# 60W_FM_PA.net
KiCad netlist of a schematic drawn in EAGLE
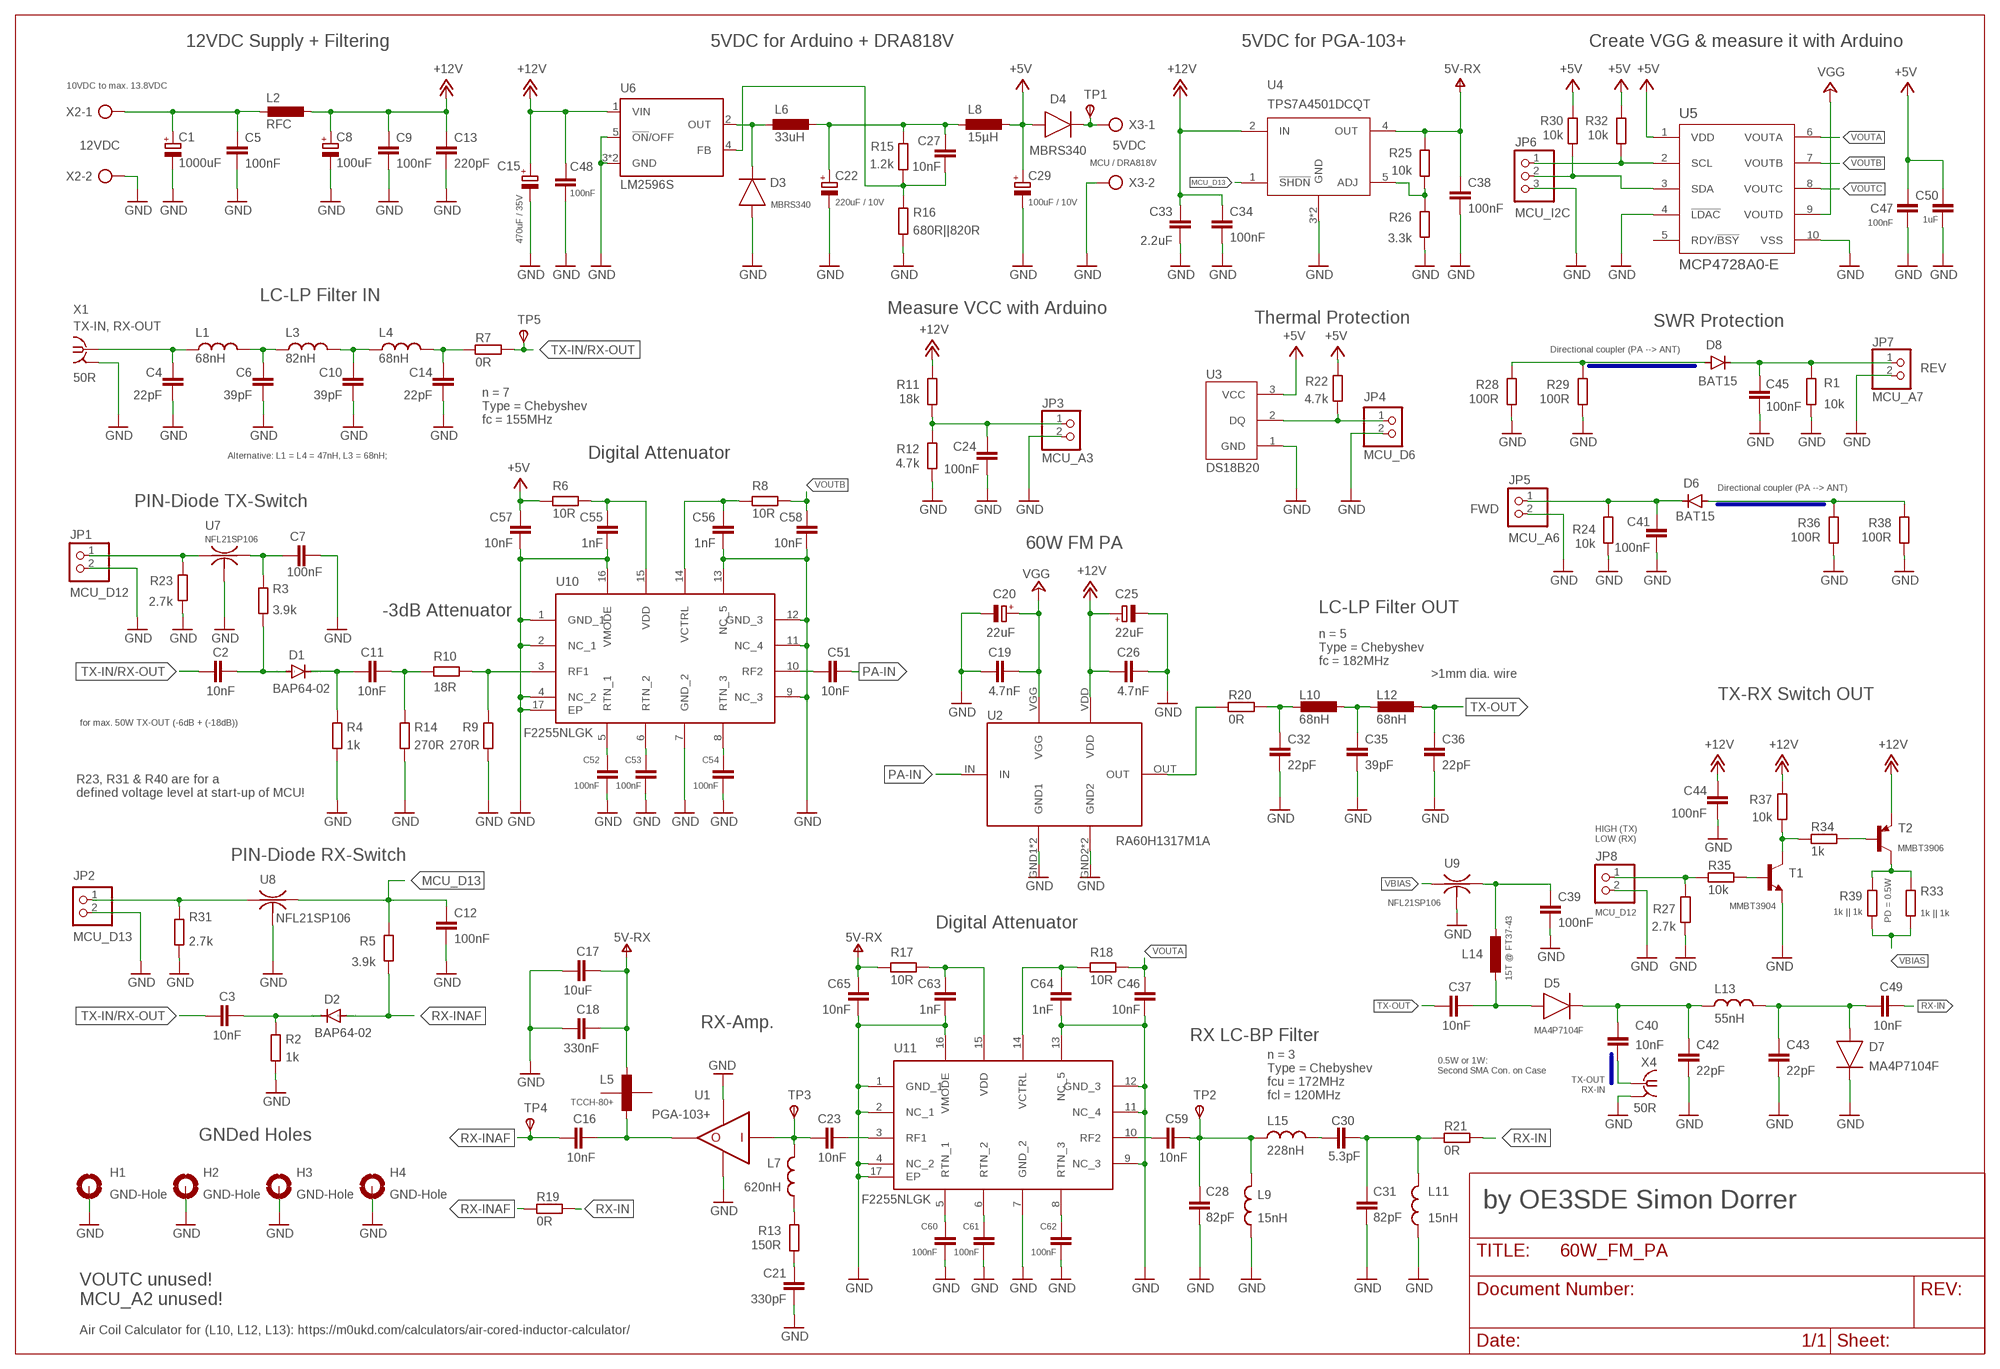
[diagram p0: schematic, sheet 1]

(export (version "E")
  (design (tool "Eeschema 10.0.6"))
  (components
    (comp (ref "C1")
      (value "1000uF")
      (footprint "eagle-import:CAPAE1030X1050N")
      (libsource (lib "eagle-import") (part "C-POLECAP-10.5MM_"))
    )
    (comp (ref "C2")
      (value "10nF")
      (footprint "eagle-import:CAPC2012X110")
      (libsource (lib "eagle-import") (part "CCHIP-0805(2012-METRIC)_"))
    )
    (comp (ref "C3")
      (value "10nF")
      (footprint "eagle-import:CAPC2012X110")
      (libsource (lib "eagle-import") (part "CCHIP-0805(2012-METRIC)_"))
    )
    (comp (ref "C4")
      (value "22pF")
      (footprint "eagle-import:CAPC2012X110")
      (libsource (lib "eagle-import") (part "CCHIP-0805(2012-METRIC)_"))
    )
    (comp (ref "C5")
      (value "100nF")
      (footprint "eagle-import:CAPC2012X110")
      (libsource (lib "eagle-import") (part "CCHIP-0805(2012-METRIC)_"))
    )
    (comp (ref "C6")
      (value "39pF")
      (footprint "eagle-import:CAPC2012X110")
      (libsource (lib "eagle-import") (part "CCHIP-0805(2012-METRIC)_"))
    )
    (comp (ref "C7")
      (value "100nF")
      (footprint "eagle-import:CAPC2012X110")
      (libsource (lib "eagle-import") (part "CCHIP-0805(2012-METRIC)_"))
    )
    (comp (ref "C8")
      (value "100uF")
      (footprint "eagle-import:CAPAE1030X1050N")
      (libsource (lib "eagle-import") (part "C-POLECAP-10.5MM_"))
    )
    (comp (ref "C9")
      (value "100nF")
      (footprint "eagle-import:CAPC2012X110")
      (libsource (lib "eagle-import") (part "CCHIP-0805(2012-METRIC)_"))
    )
    (comp (ref "C10")
      (value "39pF")
      (footprint "eagle-import:CAPC2012X110")
      (libsource (lib "eagle-import") (part "CCHIP-0805(2012-METRIC)_"))
    )
    (comp (ref "C11")
      (value "10nF")
      (footprint "eagle-import:CAPC2012X110")
      (libsource (lib "eagle-import") (part "CCHIP-0805(2012-METRIC)_"))
    )
    (comp (ref "C12")
      (value "100nF")
      (footprint "eagle-import:CAPC2012X110")
      (libsource (lib "eagle-import") (part "CCHIP-0805(2012-METRIC)_"))
    )
    (comp (ref "C13")
      (value "220pF")
      (footprint "eagle-import:CAPC2012X110")
      (libsource (lib "eagle-import") (part "CCHIP-0805(2012-METRIC)_"))
    )
    (comp (ref "C14")
      (value "22pF")
      (footprint "eagle-import:CAPC2012X110")
      (libsource (lib "eagle-import") (part "CCHIP-0805(2012-METRIC)_"))
    )
    (comp (ref "C15")
      (value "470uF / 35V")
      (footprint "eagle-import:CAPAE1030X1050N")
      (libsource (lib "eagle-import") (part "C-POLECAP-10.5MM_"))
    )
    (comp (ref "C16")
      (value "10nF")
      (footprint "eagle-import:CAPC2012X110")
      (libsource (lib "eagle-import") (part "CCHIP-0805(2012-METRIC)_"))
    )
    (comp (ref "C17")
      (value "10uF")
      (footprint "eagle-import:CAPC2012X110")
      (libsource (lib "eagle-import") (part "CCHIP-0805(2012-METRIC)_"))
    )
    (comp (ref "C18")
      (value "330nF")
      (footprint "eagle-import:CAPC2012X110")
      (libsource (lib "eagle-import") (part "CCHIP-0805(2012-METRIC)_"))
    )
    (comp (ref "C19")
      (value "4.7nF")
      (footprint "eagle-import:CAPC2012X110")
      (libsource (lib "eagle-import") (part "CCHIP-0805(2012-METRIC)_"))
    )
    (comp (ref "C20")
      (value "22uF")
      (footprint "eagle-import:SMC_D")
      (libsource (lib "eagle-import") (part "CPOL-EUSMCD"))
    )
    (comp (ref "C21")
      (value "330pF")
      (footprint "eagle-import:CAPC2012X110")
      (libsource (lib "eagle-import") (part "CCHIP-0805(2012-METRIC)_"))
    )
    (comp (ref "C22")
      (value "220uF / 10V")
      (footprint "eagle-import:CAPMP7343X310N")
      (libsource (lib "eagle-import") (part "C-POLTANTALUM-2917(7343-METRIC)_"))
    )
    (comp (ref "C23")
      (value "10nF")
      (footprint "eagle-import:CAPC2012X110")
      (libsource (lib "eagle-import") (part "CCHIP-0805(2012-METRIC)_"))
    )
    (comp (ref "C24")
      (value "100nF")
      (footprint "eagle-import:CAPC2012X110")
      (libsource (lib "eagle-import") (part "CCHIP-0805(2012-METRIC)_"))
    )
    (comp (ref "C25")
      (value "22uF")
      (footprint "eagle-import:SMC_D")
      (libsource (lib "eagle-import") (part "CPOL-EUSMCD"))
    )
    (comp (ref "C26")
      (value "4.7nF")
      (footprint "eagle-import:CAPC2012X110")
      (libsource (lib "eagle-import") (part "CCHIP-0805(2012-METRIC)_"))
    )
    (comp (ref "C27")
      (value "10nF")
      (footprint "eagle-import:CAPC2012X110")
      (libsource (lib "eagle-import") (part "CCHIP-0805(2012-METRIC)_"))
    )
    (comp (ref "C28")
      (value "82pF")
      (footprint "eagle-import:CAPC2012X110")
      (libsource (lib "eagle-import") (part "CCHIP-0805(2012-METRIC)_"))
    )
    (comp (ref "C29")
      (value "100uF / 10V")
      (footprint "eagle-import:CAPMP7343X310N")
      (libsource (lib "eagle-import") (part "C-POLTANTALUM-2917(7343-METRIC)_"))
    )
    (comp (ref "C30")
      (value "5.3pF")
      (footprint "eagle-import:CAPC2012X110")
      (libsource (lib "eagle-import") (part "CCHIP-0805(2012-METRIC)_"))
    )
    (comp (ref "C31")
      (value "82pF")
      (footprint "eagle-import:CAPC2012X110")
      (libsource (lib "eagle-import") (part "CCHIP-0805(2012-METRIC)_"))
    )
    (comp (ref "C32")
      (value "22pF")
      (footprint "eagle-import:CAPC3216X135")
      (libsource (lib "eagle-import") (part "CCHIP-1206(3216-METRIC)_"))
    )
    (comp (ref "C33")
      (value "2.2uF")
      (footprint "eagle-import:CAPC2012X110")
      (libsource (lib "eagle-import") (part "CCHIP-0805(2012-METRIC)_"))
    )
    (comp (ref "C34")
      (value "100nF")
      (footprint "eagle-import:CAPC2012X110")
      (libsource (lib "eagle-import") (part "CCHIP-0805(2012-METRIC)_"))
    )
    (comp (ref "C35")
      (value "39pF")
      (footprint "eagle-import:CAPC3216X135")
      (libsource (lib "eagle-import") (part "CCHIP-1206(3216-METRIC)_"))
    )
    (comp (ref "C36")
      (value "22pF")
      (footprint "eagle-import:CAPC3216X135")
      (libsource (lib "eagle-import") (part "CCHIP-1206(3216-METRIC)_"))
    )
    (comp (ref "C37")
      (value "10nF")
      (footprint "eagle-import:CAPC3216X135")
      (libsource (lib "eagle-import") (part "CCHIP-1206(3216-METRIC)_"))
    )
    (comp (ref "C38")
      (value "100nF")
      (footprint "eagle-import:CAPC2012X110")
      (libsource (lib "eagle-import") (part "CCHIP-0805(2012-METRIC)_"))
    )
    (comp (ref "C39")
      (value "100nF")
      (footprint "eagle-import:CAPC2012X110")
      (libsource (lib "eagle-import") (part "CCHIP-0805(2012-METRIC)_"))
    )
    (comp (ref "C40")
      (value "10nF")
      (footprint "eagle-import:CAPC3216X135")
      (libsource (lib "eagle-import") (part "CCHIP-1206(3216-METRIC)_"))
    )
    (comp (ref "C41")
      (value "100nF")
      (footprint "eagle-import:CAPC2012X110")
      (libsource (lib "eagle-import") (part "CCHIP-0805(2012-METRIC)_"))
    )
    (comp (ref "C42")
      (value "22pF")
      (footprint "eagle-import:CAPC3216X135")
      (libsource (lib "eagle-import") (part "CCHIP-1206(3216-METRIC)_"))
    )
    (comp (ref "C43")
      (value "22pF")
      (footprint "eagle-import:CAPC3216X135")
      (libsource (lib "eagle-import") (part "CCHIP-1206(3216-METRIC)_"))
    )
    (comp (ref "C44")
      (value "100nF")
      (footprint "eagle-import:CAPC2012X110")
      (libsource (lib "eagle-import") (part "CCHIP-0805(2012-METRIC)_"))
    )
    (comp (ref "C45")
      (value "100nF")
      (footprint "eagle-import:CAPC2012X110")
      (libsource (lib "eagle-import") (part "CCHIP-0805(2012-METRIC)_"))
    )
    (comp (ref "C46")
      (value "10nF")
      (footprint "eagle-import:CAPC2012X110")
      (libsource (lib "eagle-import") (part "CCHIP-0805(2012-METRIC)_"))
    )
    (comp (ref "C47")
      (value "100nF")
      (footprint "eagle-import:CAPC2012X110")
      (libsource (lib "eagle-import") (part "CCHIP-0805(2012-METRIC)_"))
    )
    (comp (ref "C48")
      (value "100nF")
      (footprint "eagle-import:CAPC2012X110")
      (libsource (lib "eagle-import") (part "CCHIP-0805(2012-METRIC)_"))
    )
    (comp (ref "C49")
      (value "10nF")
      (footprint "eagle-import:CAPC3216X135")
      (libsource (lib "eagle-import") (part "CCHIP-1206(3216-METRIC)_"))
    )
    (comp (ref "C50")
      (value "1uF")
      (footprint "eagle-import:CAPC2012X110")
      (libsource (lib "eagle-import") (part "CCHIP-0805(2012-METRIC)_"))
    )
    (comp (ref "C51")
      (value "10nF")
      (footprint "eagle-import:CAPC2012X110")
      (libsource (lib "eagle-import") (part "CCHIP-0805(2012-METRIC)_"))
    )
    (comp (ref "C52")
      (value "100nF")
      (footprint "eagle-import:CAPC1608X85")
      (libsource (lib "eagle-import") (part "CCHIP-0603(1608-METRIC)_"))
    )
    (comp (ref "C53")
      (value "100nF")
      (footprint "eagle-import:CAPC1608X85")
      (libsource (lib "eagle-import") (part "CCHIP-0603(1608-METRIC)_"))
    )
    (comp (ref "C54")
      (value "100nF")
      (footprint "eagle-import:CAPC1608X85")
      (libsource (lib "eagle-import") (part "CCHIP-0603(1608-METRIC)_"))
    )
    (comp (ref "C55")
      (value "1nF")
      (footprint "eagle-import:CAPC2012X110")
      (libsource (lib "eagle-import") (part "CCHIP-0805(2012-METRIC)_"))
    )
    (comp (ref "C56")
      (value "1nF")
      (footprint "eagle-import:CAPC2012X110")
      (libsource (lib "eagle-import") (part "CCHIP-0805(2012-METRIC)_"))
    )
    (comp (ref "C57")
      (value "10nF")
      (footprint "eagle-import:CAPC2012X110")
      (libsource (lib "eagle-import") (part "CCHIP-0805(2012-METRIC)_"))
    )
    (comp (ref "C58")
      (value "10nF")
      (footprint "eagle-import:CAPC2012X110")
      (libsource (lib "eagle-import") (part "CCHIP-0805(2012-METRIC)_"))
    )
    (comp (ref "C59")
      (value "10nF")
      (footprint "eagle-import:CAPC2012X110")
      (libsource (lib "eagle-import") (part "CCHIP-0805(2012-METRIC)_"))
    )
    (comp (ref "C60")
      (value "100nF")
      (footprint "eagle-import:CAPC1608X85")
      (libsource (lib "eagle-import") (part "CCHIP-0603(1608-METRIC)_"))
    )
    (comp (ref "C61")
      (value "100nF")
      (footprint "eagle-import:CAPC1608X85")
      (libsource (lib "eagle-import") (part "CCHIP-0603(1608-METRIC)_"))
    )
    (comp (ref "C62")
      (value "100nF")
      (footprint "eagle-import:CAPC1608X85")
      (libsource (lib "eagle-import") (part "CCHIP-0603(1608-METRIC)_"))
    )
    (comp (ref "C63")
      (value "1nF")
      (footprint "eagle-import:CAPC2012X110")
      (libsource (lib "eagle-import") (part "CCHIP-0805(2012-METRIC)_"))
    )
    (comp (ref "C64")
      (value "1nF")
      (footprint "eagle-import:CAPC2012X110")
      (libsource (lib "eagle-import") (part "CCHIP-0805(2012-METRIC)_"))
    )
    (comp (ref "C65")
      (value "10nF")
      (footprint "eagle-import:CAPC2012X110")
      (libsource (lib "eagle-import") (part "CCHIP-0805(2012-METRIC)_"))
    )
    (comp (ref "D1")
      (value "BAP64-02")
      (footprint "eagle-import:SOD523")
      (libsource (lib "eagle-import") (part "DIODE-SOD523"))
    )
    (comp (ref "D2")
      (value "BAP64-02")
      (footprint "eagle-import:SOD523")
      (libsource (lib "eagle-import") (part "DIODE-SOD523"))
    )
    (comp (ref "D3")
      (value "MBRS340")
      (footprint "eagle-import:DIOM7959X625N")
      (libsource (lib "eagle-import") (part "DIODEDO-214AB(SMC)"))
    )
    (comp (ref "D4")
      (value "MBRS340")
      (footprint "eagle-import:DIOM7959X625N")
      (libsource (lib "eagle-import") (part "DIODEDO-214AB(SMC)"))
    )
    (comp (ref "D5")
      (value "MA4P7104F")
      (footprint "eagle-import:SODFL5336X110")
      (libsource (lib "eagle-import") (part "DIODEDO-221-AA_"))
    )
    (comp (ref "D6")
      (value "BAT15")
      (footprint "eagle-import:SOD-323")
      (fields
        (field (name "DIGIKEY_PART_NUMBER") "1N4148WSFSTR-ND")
        (field (name "MANUFACTURER") "Diodes Incorporated")
        (field (name "MPN") "1N4148WS")
        (field (name "CREATED_BY") "PCBLayout.com")
      )
      (libsource (lib "eagle-import") (part "1N4148WS"))
    )
    (comp (ref "D7")
      (value "MA4P7104F")
      (footprint "eagle-import:SODFL5336X110")
      (libsource (lib "eagle-import") (part "DIODEDO-221-AA_"))
    )
    (comp (ref "D8")
      (value "BAT15")
      (footprint "eagle-import:SOD-323")
      (fields
        (field (name "DIGIKEY_PART_NUMBER") "1N4148WSFSTR-ND")
        (field (name "MANUFACTURER") "Diodes Incorporated")
        (field (name "MPN") "1N4148WS")
        (field (name "CREATED_BY") "PCBLayout.com")
      )
      (libsource (lib "eagle-import") (part "1N4148WS"))
    )
    (comp (ref "H1")
      (value "GND-Hole")
      (footprint "eagle-import:3,0-PAD")
      (libsource (lib "eagle-import") (part "MOUNT-PAD-ROUND3.0"))
    )
    (comp (ref "H2")
      (value "GND-Hole")
      (footprint "eagle-import:3,0-PAD")
      (libsource (lib "eagle-import") (part "MOUNT-PAD-ROUND3.0"))
    )
    (comp (ref "H3")
      (value "GND-Hole")
      (footprint "eagle-import:3,0-PAD")
      (libsource (lib "eagle-import") (part "MOUNT-PAD-ROUND3.0"))
    )
    (comp (ref "H4")
      (value "GND-Hole")
      (footprint "eagle-import:3,0-PAD")
      (libsource (lib "eagle-import") (part "MOUNT-PAD-ROUND3.0"))
    )
    (comp (ref "JP1")
      (value "MCU_D12")
      (footprint "eagle-import:1X02")
      (libsource (lib "eagle-import") (part "PINHD-1X2"))
    )
    (comp (ref "JP2")
      (value "MCU_D13")
      (footprint "eagle-import:1X02")
      (libsource (lib "eagle-import") (part "PINHD-1X2"))
    )
    (comp (ref "JP3")
      (value "MCU_A3")
      (footprint "eagle-import:1X02")
      (libsource (lib "eagle-import") (part "PINHD-1X2"))
    )
    (comp (ref "JP4")
      (value "MCU_D6")
      (footprint "eagle-import:1X02")
      (libsource (lib "eagle-import") (part "PINHD-1X2"))
    )
    (comp (ref "JP5")
      (value "MCU_A6")
      (footprint "eagle-import:1X02")
      (libsource (lib "eagle-import") (part "PINHD-1X2"))
    )
    (comp (ref "JP6")
      (value "MCU_I2C")
      (footprint "eagle-import:1X03")
      (libsource (lib "eagle-import") (part "PINHD-1X3"))
    )
    (comp (ref "JP7")
      (value "MCU_A7")
      (footprint "eagle-import:1X02")
      (libsource (lib "eagle-import") (part "PINHD-1X2"))
    )
    (comp (ref "JP8")
      (value "MCU_D12")
      (footprint "eagle-import:1X02")
      (libsource (lib "eagle-import") (part "PINHD-1X2"))
    )
    (comp (ref "L1")
      (value "68nH")
      (footprint "eagle-import:INDC2009X120")
      (libsource (lib "eagle-import") (part "LCHIP-0805(2012-METRIC)_"))
    )
    (comp (ref "L2")
      (value "RFC")
      (footprint "eagle-import:T50-6SMD")
      (libsource (lib "eagle-import") (part "T50-6"))
    )
    (comp (ref "L3")
      (value "82nH")
      (footprint "eagle-import:INDC2009X120")
      (libsource (lib "eagle-import") (part "LCHIP-0805(2012-METRIC)_"))
    )
    (comp (ref "L4")
      (value "68nH")
      (footprint "eagle-import:INDC2009X120")
      (libsource (lib "eagle-import") (part "LCHIP-0805(2012-METRIC)_"))
    )
    (comp (ref "L5")
      (value "TCCH-80+")
      (footprint "eagle-import:TCCH-80")
      (libsource (lib "eagle-import") (part "TCCH-80+"))
    )
    (comp (ref "L6")
      (value "33uH")
      (footprint "eagle-import:1260")
      (libsource (lib "eagle-import") (part "L-EU"))
    )
    (comp (ref "L7")
      (value "620nH")
      (footprint "eagle-import:INDC2009X120")
      (libsource (lib "eagle-import") (part "LCHIP-0805(2012-METRIC)_"))
    )
    (comp (ref "L8")
      (value "15µH")
      (footprint "eagle-import:1260")
      (libsource (lib "eagle-import") (part "L-EU"))
    )
    (comp (ref "L9")
      (value "15nH")
      (footprint "eagle-import:INDC3216X190")
      (libsource (lib "eagle-import") (part "LCHIP-1206(3216-METRIC)_"))
    )
    (comp (ref "L10")
      (value "68nH")
      (footprint "eagle-import:AIR-COIL-SMD")
      (libsource (lib "eagle-import") (part "AIR-COIL"))
    )
    (comp (ref "L11")
      (value "15nH")
      (footprint "eagle-import:INDC3216X190")
      (libsource (lib "eagle-import") (part "LCHIP-1206(3216-METRIC)_"))
    )
    (comp (ref "L12")
      (value "68nH")
      (footprint "eagle-import:AIR-COIL-SMD")
      (libsource (lib "eagle-import") (part "AIR-COIL"))
    )
    (comp (ref "L13")
      (value "55nH")
      (footprint "eagle-import:INDC3216X190")
      (libsource (lib "eagle-import") (part "LCHIP-1206(3216-METRIC)_"))
    )
    (comp (ref "L14")
      (value "15T @ FT37-43")
      (footprint "eagle-import:AIR-COIL-SMD")
      (libsource (lib "eagle-import") (part "AIR-COIL"))
    )
    (comp (ref "L15")
      (value "228nH")
      (footprint "eagle-import:INDC3216X190")
      (libsource (lib "eagle-import") (part "LCHIP-1206(3216-METRIC)_"))
    )
    (comp (ref "R1")
      (value "10k")
      (footprint "eagle-import:RESC2012X65")
      (libsource (lib "eagle-import") (part "RCHIP-0805(2012-METRIC)_"))
    )
    (comp (ref "R2")
      (value "1k")
      (footprint "eagle-import:RESC2012X65")
      (libsource (lib "eagle-import") (part "RCHIP-0805(2012-METRIC)_"))
    )
    (comp (ref "R3")
      (value "3.9k")
      (footprint "eagle-import:RESC2012X65")
      (libsource (lib "eagle-import") (part "RCHIP-0805(2012-METRIC)_"))
    )
    (comp (ref "R4")
      (value "1k")
      (footprint "eagle-import:RESC2012X65")
      (libsource (lib "eagle-import") (part "RCHIP-0805(2012-METRIC)_"))
    )
    (comp (ref "R5")
      (value "3.9k")
      (footprint "eagle-import:RESC2012X65")
      (libsource (lib "eagle-import") (part "RCHIP-0805(2012-METRIC)_"))
    )
    (comp (ref "R6")
      (value "10R")
      (footprint "eagle-import:RESC2012X65")
      (libsource (lib "eagle-import") (part "RCHIP-0805(2012-METRIC)_"))
    )
    (comp (ref "R7")
      (value "0R")
      (footprint "eagle-import:RESC2012X65")
      (libsource (lib "eagle-import") (part "RCHIP-0805(2012-METRIC)_"))
    )
    (comp (ref "R8")
      (value "10R")
      (footprint "eagle-import:RESC2012X65")
      (libsource (lib "eagle-import") (part "RCHIP-0805(2012-METRIC)_"))
    )
    (comp (ref "R9")
      (value "270R")
      (footprint "eagle-import:RESC2012X65")
      (libsource (lib "eagle-import") (part "RCHIP-0805(2012-METRIC)_"))
    )
    (comp (ref "R10")
      (value "18R")
      (footprint "eagle-import:RESC2012X65")
      (libsource (lib "eagle-import") (part "RCHIP-0805(2012-METRIC)_"))
    )
    (comp (ref "R11")
      (value "18k")
      (footprint "eagle-import:RESC2012X65")
      (libsource (lib "eagle-import") (part "RCHIP-0805(2012-METRIC)_"))
    )
    (comp (ref "R12")
      (value "4.7k")
      (footprint "eagle-import:RESC2012X65")
      (libsource (lib "eagle-import") (part "RCHIP-0805(2012-METRIC)_"))
    )
    (comp (ref "R13")
      (value "150R")
      (footprint "eagle-import:RESC2012X65")
      (libsource (lib "eagle-import") (part "RCHIP-0805(2012-METRIC)_"))
    )
    (comp (ref "R14")
      (value "270R")
      (footprint "eagle-import:RESC2012X65")
      (libsource (lib "eagle-import") (part "RCHIP-0805(2012-METRIC)_"))
    )
    (comp (ref "R15")
      (value "1.2k")
      (footprint "eagle-import:RESC2012X65")
      (libsource (lib "eagle-import") (part "RCHIP-0805(2012-METRIC)_"))
    )
    (comp (ref "R16")
      (value "680R||820R")
      (footprint "eagle-import:RESC2012X65")
      (libsource (lib "eagle-import") (part "RCHIP-0805(2012-METRIC)_"))
    )
    (comp (ref "R17")
      (value "10R")
      (footprint "eagle-import:RESC2012X65")
      (libsource (lib "eagle-import") (part "RCHIP-0805(2012-METRIC)_"))
    )
    (comp (ref "R18")
      (value "10R")
      (footprint "eagle-import:RESC2012X65")
      (libsource (lib "eagle-import") (part "RCHIP-0805(2012-METRIC)_"))
    )
    (comp (ref "R19")
      (value "0R")
      (footprint "eagle-import:RESC2012X65")
      (libsource (lib "eagle-import") (part "RCHIP-0805(2012-METRIC)_"))
    )
    (comp (ref "R20")
      (value "0R")
      (footprint "eagle-import:RESC3216X70")
      (libsource (lib "eagle-import") (part "RCHIP-1206(3216-METRIC)_"))
    )
    (comp (ref "R21")
      (value "0R")
      (footprint "eagle-import:RESC2012X65")
      (libsource (lib "eagle-import") (part "RCHIP-0805(2012-METRIC)_"))
    )
    (comp (ref "R22")
      (value "4.7k")
      (footprint "eagle-import:RESC2012X65")
      (libsource (lib "eagle-import") (part "RCHIP-0805(2012-METRIC)_"))
    )
    (comp (ref "R23")
      (value "2.7k")
      (footprint "eagle-import:RESC2012X65")
      (libsource (lib "eagle-import") (part "RCHIP-0805(2012-METRIC)_"))
    )
    (comp (ref "R24")
      (value "10k")
      (footprint "eagle-import:RESC2012X65")
      (libsource (lib "eagle-import") (part "RCHIP-0805(2012-METRIC)_"))
    )
    (comp (ref "R25")
      (value "10k")
      (footprint "eagle-import:RESC2012X65")
      (libsource (lib "eagle-import") (part "RCHIP-0805(2012-METRIC)_"))
    )
    (comp (ref "R26")
      (value "3.3k")
      (footprint "eagle-import:RESC2012X65")
      (libsource (lib "eagle-import") (part "RCHIP-0805(2012-METRIC)_"))
    )
    (comp (ref "R27")
      (value "2.7k")
      (footprint "eagle-import:RESC2012X65")
      (libsource (lib "eagle-import") (part "RCHIP-0805(2012-METRIC)_"))
    )
    (comp (ref "R28")
      (value "100R")
      (footprint "eagle-import:RESC2012X65")
      (libsource (lib "eagle-import") (part "RCHIP-0805(2012-METRIC)_"))
    )
    (comp (ref "R29")
      (value "100R")
      (footprint "eagle-import:RESC2012X65")
      (libsource (lib "eagle-import") (part "RCHIP-0805(2012-METRIC)_"))
    )
    (comp (ref "R30")
      (value "10k")
      (footprint "eagle-import:RESC2012X65")
      (libsource (lib "eagle-import") (part "RCHIP-0805(2012-METRIC)_"))
    )
    (comp (ref "R31")
      (value "2.7k")
      (footprint "eagle-import:RESC2012X65")
      (libsource (lib "eagle-import") (part "RCHIP-0805(2012-METRIC)_"))
    )
    (comp (ref "R32")
      (value "10k")
      (footprint "eagle-import:RESC2012X65")
      (libsource (lib "eagle-import") (part "RCHIP-0805(2012-METRIC)_"))
    )
    (comp (ref "R33")
      (value "1k || 1k")
      (footprint "eagle-import:RESC2012X65")
      (libsource (lib "eagle-import") (part "RCHIP-0805(2012-METRIC)_"))
    )
    (comp (ref "R34")
      (value "1k")
      (footprint "eagle-import:RESC2012X65")
      (libsource (lib "eagle-import") (part "RCHIP-0805(2012-METRIC)_"))
    )
    (comp (ref "R35")
      (value "10k")
      (footprint "eagle-import:RESC2012X65")
      (libsource (lib "eagle-import") (part "RCHIP-0805(2012-METRIC)_"))
    )
    (comp (ref "R36")
      (value "100R")
      (footprint "eagle-import:RESC2012X65")
      (libsource (lib "eagle-import") (part "RCHIP-0805(2012-METRIC)_"))
    )
    (comp (ref "R37")
      (value "10k")
      (footprint "eagle-import:RESC2012X65")
      (libsource (lib "eagle-import") (part "RCHIP-0805(2012-METRIC)_"))
    )
    (comp (ref "R38")
      (value "100R")
      (footprint "eagle-import:RESC2012X65")
      (libsource (lib "eagle-import") (part "RCHIP-0805(2012-METRIC)_"))
    )
    (comp (ref "R39")
      (value "1k || 1k")
      (footprint "eagle-import:RESC2012X65")
      (libsource (lib "eagle-import") (part "RCHIP-0805(2012-METRIC)_"))
    )
    (comp (ref "T1")
      (value "MMBT3904")
      (footprint "eagle-import:SOT23-BEC")
      (libsource (lib "eagle-import") (part "-NPN-SOT23-BECMMBT3904LT1"))
    )
    (comp (ref "T2")
      (value "MMBT3906")
      (footprint "eagle-import:SOT23-BEC")
      (libsource (lib "eagle-import") (part "MMBT3906SMDLT1"))
    )
    (comp (ref "TP1")
      (value "TPSTP10SQ")
      (footprint "eagle-import:TP10SQ")
      (libsource (lib "eagle-import") (part "TPSTP10SQ"))
    )
    (comp (ref "TP2")
      (value "TPSTP10SQ")
      (footprint "eagle-import:TP10SQ")
      (libsource (lib "eagle-import") (part "TPSTP10SQ"))
    )
    (comp (ref "TP3")
      (value "TPSTP10SQ")
      (footprint "eagle-import:TP10SQ")
      (libsource (lib "eagle-import") (part "TPSTP10SQ"))
    )
    (comp (ref "TP4")
      (value "TPSTP10SQ")
      (footprint "eagle-import:TP10SQ")
      (libsource (lib "eagle-import") (part "TPSTP10SQ"))
    )
    (comp (ref "TP5")
      (value "TPSTP10SQ")
      (footprint "eagle-import:TP10SQ")
      (libsource (lib "eagle-import") (part "TPSTP10SQ"))
    )
    (comp (ref "U1")
      (value "PGA-103+")
      (footprint "eagle-import:SOT89")
      (libsource (lib "eagle-import") (part "PGA-103+"))
    )
    (comp (ref "U2")
      (value "RA60H1317M1A")
      (footprint "eagle-import:RA60H1317M1A")
      (libsource (lib "eagle-import") (part "RA60H1317M1A"))
    )
    (comp (ref "U3")
      (value "DS18B20")
      (footprint "eagle-import:21-0248A_MXM")
      (fields (field (name "MANUFACTURER_PART_NUMBER") "DS1810-10"))
      (libsource (lib "eagle-import") (part "DS1810-10"))
    )
    (comp (ref "U4")
      (value "TPS7A4501DCQT")
      (footprint "eagle-import:DCQ6")
      (fields
        (field (name "GENERIC_PART_NUMBER") "TPS7A4533")
        (field (name "MANUFACTURER") "Texas Instruments")
      )
      (libsource (lib "eagle-import") (part "TPS7A4501DCQT"))
    )
    (comp (ref "U5")
      (value "MCP4728A0-E")
      (footprint "eagle-import:MSOP10_MC_MCH-M")
      (fields
        (field (name "MANUFACTURER_PART_NUMBER") "MCP4728A0-E/UN")
        (field (name "COPYRIGHT") "Copyright (C) 2018 Accelerated Designs. All rights reserved")
      )
      (libsource (lib "eagle-import") (part "MCP4728A0-E/UNMSOP10_MC_MCH-M"))
    )
    (comp (ref "U6")
      (value "LM2596S")
      (footprint "eagle-import:TO263-5")
      (fields (field (name "MF") "NATIONAL SEMICONDUCTOR") (field (name "MPN") "LM2596S-ADJ/NOPB"))
      (libsource (lib "eagle-import") (part "LM2596S"))
    )
    (comp (ref "U7")
      (value "NFL21SP106")
      (footprint "eagle-import:NFM21C")
      (libsource (lib "eagle-import") (part "NFL21SP106"))
    )
    (comp (ref "U8")
      (value "NFL21SP106")
      (footprint "eagle-import:NFM21C")
      (libsource (lib "eagle-import") (part "NFL21SP106"))
    )
    (comp (ref "U9")
      (value "NFL21SP106")
      (footprint "eagle-import:NFM21C")
      (libsource (lib "eagle-import") (part "NFL21SP106"))
    )
    (comp (ref "U10")
      (value "F2255NLGK")
      (footprint "eagle-import:QFN50P300X300X100-17N")
      (fields (field (name "MOUSER_PART_NUMBER") "972-F2255NLGK"))
      (libsource (lib "eagle-import") (part "F2255NLGK"))
    )
    (comp (ref "U11")
      (value "F2255NLGK")
      (footprint "eagle-import:QFN50P300X300X100-17N")
      (fields (field (name "MOUSER_PART_NUMBER") "972-F2255NLGK"))
      (libsource (lib "eagle-import") (part "F2255NLGK"))
    )
    (comp (ref "X1")
      (value "TX-IN, RX-OUT")
      (footprint "eagle-import:J502-ND-142-0711-821_826")
      (fields (field (name "MF") "JOHNSON COMPONENTS") (field (name "MPN") "142-0711-821"))
      (libsource (lib "eagle-import") (part "SMA-142-0711-821/826"))
    )
    (comp (ref "X2")
      (value "12VDC")
      (footprint "eagle-import:AK300_2")
      (libsource (lib "eagle-import") (part "AK300/2"))
    )
    (comp (ref "X3")
      (value "5VDC")
      (footprint "eagle-import:AK300_2")
      (libsource (lib "eagle-import") (part "AK300/2"))
    )
    (comp (ref "X4")
      (value "50R")
      (footprint "eagle-import:J502-ND-142-0711-821_826")
      (fields (field (name "MF") "JOHNSON COMPONENTS") (field (name "MPN") "142-0711-821"))
      (libsource (lib "eagle-import") (part "SMA-142-0711-821/826"))
    )
  )
  (nets
    (net (code "4") (name "+5V") (class "Default")
      (node (ref "C29") (pin "1") (pinfunction "+_1") (pintype "passive"))
      (node (ref "C47") (pin "2") (pinfunction "2_2") (pintype "passive"))
      (node (ref "C50") (pin "2") (pinfunction "2_2") (pintype "passive"))
      (node (ref "C57") (pin "1") (pinfunction "1_1") (pintype "passive"))
      (node (ref "D4") (pin "2") (pinfunction "A_2") (pintype "passive"))
      (node (ref "L8") (pin "-") (pinfunction "2_-") (pintype "passive"))
      (node (ref "R22") (pin "2") (pinfunction "2_2") (pintype "passive"))
      (node (ref "R30") (pin "1") (pinfunction "1_1") (pintype "passive"))
      (node (ref "R32") (pin "1") (pinfunction "1_1") (pintype "passive"))
      (node (ref "R6") (pin "1") (pinfunction "1_1") (pintype "passive"))
      (node (ref "U3") (pin "3") (pinfunction "VCC_3") (pintype "power_in"))
      (node (ref "U5") (pin "1") (pinfunction "VDD_1") (pintype "power_in"))
    )
    (net (code "5") (name "+12V") (class "Default")
      (node (ref "C13") (pin "2") (pinfunction "2_2") (pintype "passive"))
      (node (ref "C15") (pin "1") (pinfunction "+_1") (pintype "passive"))
      (node (ref "C25") (pin "+") (pinfunction "+_+") (pintype "passive"))
      (node (ref "C26") (pin "1") (pinfunction "1_1") (pintype "passive"))
      (node (ref "C33") (pin "2") (pinfunction "2_2") (pintype "passive"))
      (node (ref "C34") (pin "2") (pinfunction "2_2") (pintype "passive"))
      (node (ref "C44") (pin "2") (pinfunction "2_2") (pintype "passive"))
      (node (ref "C48") (pin "2") (pinfunction "2_2") (pintype "passive"))
      (node (ref "C8") (pin "1") (pinfunction "+_1") (pintype "passive"))
      (node (ref "C9") (pin "2") (pinfunction "2_2") (pintype "passive"))
      (node (ref "L2") (pin "P$2") (pinfunction "2_P$2") (pintype "passive"))
      (node (ref "R11") (pin "2") (pinfunction "2_2") (pintype "passive"))
      (node (ref "R37") (pin "1") (pinfunction "1_1") (pintype "passive"))
      (node (ref "T2") (pin "E") (pinfunction "E_E") (pintype "passive"))
      (node (ref "U2") (pin "VDD") (pinfunction "VDD_VDD") (pintype "power_in"))
      (node (ref "U4") (pin "2") (pinfunction "IN_2") (pintype "input"))
      (node (ref "U6") (pin "1") (pinfunction "VIN_1") (pintype "input"))
    )
    (net (code "7") (name "5V-RX") (class "Default")
      (node (ref "C17") (pin "1") (pinfunction "1_1") (pintype "passive"))
      (node (ref "C18") (pin "1") (pinfunction "1_1") (pintype "passive"))
      (node (ref "C38") (pin "2") (pinfunction "2_2") (pintype "passive"))
      (node (ref "C65") (pin "1") (pinfunction "1_1") (pintype "passive"))
      (node (ref "L5") (pin "DC") (pinfunction "DC_DC") (pintype "passive"))
      (node (ref "R17") (pin "1") (pinfunction "1_1") (pintype "passive"))
      (node (ref "R25") (pin "1") (pinfunction "1_1") (pintype "passive"))
      (node (ref "U4") (pin "4") (pinfunction "OUT_4") (pintype "output"))
    )
    (net (code "8") (name "GND") (class "Default")
      (node (ref "C1") (pin "2") (pinfunction "-_2") (pintype "passive"))
      (node (ref "C10") (pin "2") (pinfunction "2_2") (pintype "passive"))
      (node (ref "C12") (pin "1") (pinfunction "1_1") (pintype "passive"))
      (node (ref "C13") (pin "1") (pinfunction "1_1") (pintype "passive"))
      (node (ref "C14") (pin "2") (pinfunction "2_2") (pintype "passive"))
      (node (ref "C15") (pin "2") (pinfunction "-_2") (pintype "passive"))
      (node (ref "C17") (pin "2") (pinfunction "2_2") (pintype "passive"))
      (node (ref "C18") (pin "2") (pinfunction "2_2") (pintype "passive"))
      (node (ref "C19") (pin "1") (pinfunction "1_1") (pintype "passive"))
      (node (ref "C20") (pin "-") (pinfunction "-_-") (pintype "passive"))
      (node (ref "C21") (pin "1") (pinfunction "1_1") (pintype "passive"))
      (node (ref "C22") (pin "2") (pinfunction "-_2") (pintype "passive"))
      (node (ref "C24") (pin "1") (pinfunction "1_1") (pintype "passive"))
      (node (ref "C25") (pin "-") (pinfunction "-_-") (pintype "passive"))
      (node (ref "C26") (pin "2") (pinfunction "2_2") (pintype "passive"))
      (node (ref "C28") (pin "2") (pinfunction "2_2") (pintype "passive"))
      (node (ref "C29") (pin "2") (pinfunction "-_2") (pintype "passive"))
      (node (ref "C31") (pin "2") (pinfunction "2_2") (pintype "passive"))
      (node (ref "C32") (pin "2") (pinfunction "2_2") (pintype "passive"))
      (node (ref "C33") (pin "1") (pinfunction "1_1") (pintype "passive"))
      (node (ref "C34") (pin "1") (pinfunction "1_1") (pintype "passive"))
      (node (ref "C35") (pin "2") (pinfunction "2_2") (pintype "passive"))
      (node (ref "C36") (pin "2") (pinfunction "2_2") (pintype "passive"))
      (node (ref "C38") (pin "1") (pinfunction "1_1") (pintype "passive"))
      (node (ref "C39") (pin "1") (pinfunction "1_1") (pintype "passive"))
      (node (ref "C4") (pin "2") (pinfunction "2_2") (pintype "passive"))
      (node (ref "C41") (pin "2") (pinfunction "2_2") (pintype "passive"))
      (node (ref "C42") (pin "2") (pinfunction "2_2") (pintype "passive"))
      (node (ref "C43") (pin "2") (pinfunction "2_2") (pintype "passive"))
      (node (ref "C44") (pin "1") (pinfunction "1_1") (pintype "passive"))
      (node (ref "C45") (pin "2") (pinfunction "2_2") (pintype "passive"))
      (node (ref "C46") (pin "2") (pinfunction "2_2") (pintype "passive"))
      (node (ref "C47") (pin "1") (pinfunction "1_1") (pintype "passive"))
      (node (ref "C48") (pin "1") (pinfunction "1_1") (pintype "passive"))
      (node (ref "C5") (pin "1") (pinfunction "1_1") (pintype "passive"))
      (node (ref "C50") (pin "1") (pinfunction "1_1") (pintype "passive"))
      (node (ref "C52") (pin "2") (pinfunction "2_2") (pintype "passive"))
      (node (ref "C53") (pin "2") (pinfunction "2_2") (pintype "passive"))
      (node (ref "C54") (pin "2") (pinfunction "2_2") (pintype "passive"))
      (node (ref "C55") (pin "2") (pinfunction "2_2") (pintype "passive"))
      (node (ref "C56") (pin "2") (pinfunction "2_2") (pintype "passive"))
      (node (ref "C57") (pin "2") (pinfunction "2_2") (pintype "passive"))
      (node (ref "C58") (pin "2") (pinfunction "2_2") (pintype "passive"))
      (node (ref "C6") (pin "2") (pinfunction "2_2") (pintype "passive"))
      (node (ref "C60") (pin "2") (pinfunction "2_2") (pintype "passive"))
      (node (ref "C61") (pin "2") (pinfunction "2_2") (pintype "passive"))
      (node (ref "C62") (pin "2") (pinfunction "2_2") (pintype "passive"))
      (node (ref "C63") (pin "2") (pinfunction "2_2") (pintype "passive"))
      (node (ref "C64") (pin "2") (pinfunction "2_2") (pintype "passive"))
      (node (ref "C65") (pin "2") (pinfunction "2_2") (pintype "passive"))
      (node (ref "C7") (pin "1") (pinfunction "1_1") (pintype "passive"))
      (node (ref "C8") (pin "2") (pinfunction "-_2") (pintype "passive"))
      (node (ref "C9") (pin "1") (pinfunction "1_1") (pintype "passive"))
      (node (ref "D3") (pin "2") (pinfunction "A_2") (pintype "passive"))
      (node (ref "D7") (pin "1") (pinfunction "C_1") (pintype "passive"))
      (node (ref "H1") (pin "B3,0") (pinfunction "MOUNT_B3,0") (pintype "passive"))
      (node (ref "H2") (pin "B3,0") (pinfunction "MOUNT_B3,0") (pintype "passive"))
      (node (ref "H3") (pin "B3,0") (pinfunction "MOUNT_B3,0") (pintype "passive"))
      (node (ref "H4") (pin "B3,0") (pinfunction "MOUNT_B3,0") (pintype "passive"))
      (node (ref "JP1") (pin "2") (pinfunction "2_2") (pintype "passive"))
      (node (ref "JP2") (pin "2") (pinfunction "2_2") (pintype "passive"))
      (node (ref "JP3") (pin "2") (pinfunction "2_2") (pintype "passive"))
      (node (ref "JP4") (pin "2") (pinfunction "2_2") (pintype "passive"))
      (node (ref "JP5") (pin "2") (pinfunction "2_2") (pintype "passive"))
      (node (ref "JP6") (pin "3") (pinfunction "3_3") (pintype "passive"))
      (node (ref "JP7") (pin "2") (pinfunction "2_2") (pintype "passive"))
      (node (ref "JP8") (pin "2") (pinfunction "2_2") (pintype "passive"))
      (node (ref "L11") (pin "1") (pinfunction "1_1") (pintype "passive"))
      (node (ref "L9") (pin "1") (pinfunction "1_1") (pintype "passive"))
      (node (ref "R1") (pin "2") (pinfunction "2_2") (pintype "passive"))
      (node (ref "R12") (pin "1") (pinfunction "1_1") (pintype "passive"))
      (node (ref "R14") (pin "2") (pinfunction "2_2") (pintype "passive"))
      (node (ref "R16") (pin "1") (pinfunction "1_1") (pintype "passive"))
      (node (ref "R2") (pin "2") (pinfunction "2_2") (pintype "passive"))
      (node (ref "R23") (pin "2") (pinfunction "2_2") (pintype "passive"))
      (node (ref "R24") (pin "1") (pinfunction "1_1") (pintype "passive"))
      (node (ref "R26") (pin "2") (pinfunction "2_2") (pintype "passive"))
      (node (ref "R27") (pin "2") (pinfunction "2_2") (pintype "passive"))
      (node (ref "R28") (pin "1") (pinfunction "1_1") (pintype "passive"))
      (node (ref "R29") (pin "1") (pinfunction "1_1") (pintype "passive"))
      (node (ref "R31") (pin "2") (pinfunction "2_2") (pintype "passive"))
      (node (ref "R36") (pin "1") (pinfunction "1_1") (pintype "passive"))
      (node (ref "R38") (pin "1") (pinfunction "1_1") (pintype "passive"))
      (node (ref "R4") (pin "2") (pinfunction "2_2") (pintype "passive"))
      (node (ref "R9") (pin "2") (pinfunction "2_2") (pintype "passive"))
      (node (ref "T1") (pin "E") (pinfunction "E_E") (pintype "passive"))
      (node (ref "U1") (pin "2") (pinfunction "GND1_2") (pintype "power_in"))
      (node (ref "U1") (pin "2@1") (pinfunction "GND2_2@1") (pintype "power_in"))
      (node (ref "U10") (pin "1") (pinfunction "GND_1_1") (pintype "bidirectional"))
      (node (ref "U10") (pin "11") (pinfunction "NC_4_11") (pintype "bidirectional"))
      (node (ref "U10") (pin "12") (pinfunction "GND_3_12") (pintype "bidirectional"))
      (node (ref "U10") (pin "13") (pinfunction "NC_5_13") (pintype "bidirectional"))
      (node (ref "U10") (pin "16") (pinfunction "VMODE_16") (pintype "bidirectional"))
      (node (ref "U10") (pin "17") (pinfunction "EP_17") (pintype "bidirectional"))
      (node (ref "U10") (pin "2") (pinfunction "NC_1_2") (pintype "bidirectional"))
      (node (ref "U10") (pin "4") (pinfunction "NC_2_4") (pintype "bidirectional"))
      (node (ref "U10") (pin "7") (pinfunction "GND_2_7") (pintype "bidirectional"))
      (node (ref "U10") (pin "9") (pinfunction "NC_3_9") (pintype "bidirectional"))
      (node (ref "U11") (pin "1") (pinfunction "GND_1_1") (pintype "bidirectional"))
      (node (ref "U11") (pin "11") (pinfunction "NC_4_11") (pintype "bidirectional"))
      (node (ref "U11") (pin "12") (pinfunction "GND_3_12") (pintype "bidirectional"))
      (node (ref "U11") (pin "13") (pinfunction "NC_5_13") (pintype "bidirectional"))
      (node (ref "U11") (pin "16") (pinfunction "VMODE_16") (pintype "bidirectional"))
      (node (ref "U11") (pin "17") (pinfunction "EP_17") (pintype "bidirectional"))
      (node (ref "U11") (pin "2") (pinfunction "NC_1_2") (pintype "bidirectional"))
      (node (ref "U11") (pin "4") (pinfunction "NC_2_4") (pintype "bidirectional"))
      (node (ref "U11") (pin "7") (pinfunction "GND_2_7") (pintype "bidirectional"))
      (node (ref "U11") (pin "9") (pinfunction "NC_3_9") (pintype "bidirectional"))
      (node (ref "U2") (pin "GND1") (pinfunction "GND1_GND1") (pintype "power_in"))
      (node (ref "U2") (pin "GND2") (pinfunction "GND2_GND2") (pintype "power_in"))
      (node (ref "U2") (pin "GND3") (pinfunction "GND1_GND3") (pintype "power_in"))
      (node (ref "U2") (pin "GND4") (pinfunction "GND2_GND4") (pintype "power_in"))
      (node (ref "U3") (pin "1") (pinfunction "GND_1") (pintype "power_in"))
      (node (ref "U4") (pin "3") (pinfunction "GND_3") (pintype "power_in"))
      (node (ref "U4") (pin "6") (pinfunction "GND_6") (pintype "power_in"))
      (node (ref "U5") (pin "10") (pinfunction "VSS_10") (pintype "power_in"))
      (node (ref "U5") (pin "4") (pinfunction "~{LDAC}_4") (pintype "input"))
      (node (ref "U6") (pin "3") (pinfunction "GND_3") (pintype "power_in"))
      (node (ref "U6") (pin "5") (pinfunction "~{ON}/OFF_5") (pintype "input"))
      (node (ref "U6") (pin "6") (pinfunction "GND_6") (pintype "power_in"))
      (node (ref "U7") (pin "2@1") (pinfunction "2_2@1") (pintype "passive"))
      (node (ref "U7") (pin "2@2") (pinfunction "2_2@2") (pintype "passive"))
      (node (ref "U8") (pin "2@1") (pinfunction "2_2@1") (pintype "passive"))
      (node (ref "U8") (pin "2@2") (pinfunction "2_2@2") (pintype "passive"))
      (node (ref "U9") (pin "2@1") (pinfunction "2_2@1") (pintype "passive"))
      (node (ref "U9") (pin "2@2") (pinfunction "2_2@2") (pintype "passive"))
      (node (ref "X1") (pin "G@1") (pinfunction "2_G@1") (pintype "passive"))
      (node (ref "X1") (pin "G@2") (pinfunction "2_G@2") (pintype "passive"))
      (node (ref "X1") (pin "G@3") (pinfunction "2_G@3") (pintype "passive"))
      (node (ref "X1") (pin "G@4") (pinfunction "2_G@4") (pintype "passive"))
      (node (ref "X2") (pin "2") (pinfunction "KL_2") (pintype "passive"))
      (node (ref "X3") (pin "2") (pinfunction "KL_2") (pintype "passive"))
      (node (ref "X4") (pin "G@1") (pinfunction "2_G@1") (pintype "passive"))
      (node (ref "X4") (pin "G@2") (pinfunction "2_G@2") (pintype "passive"))
      (node (ref "X4") (pin "G@3") (pinfunction "2_G@3") (pintype "passive"))
      (node (ref "X4") (pin "G@4") (pinfunction "2_G@4") (pintype "passive"))
    )
    (net (code "9") (name "MCU_D13") (class "Default")
      (node (ref "C12") (pin "2") (pinfunction "2_2") (pintype "passive"))
      (node (ref "R5") (pin "1") (pinfunction "1_1") (pintype "passive"))
      (node (ref "U4") (pin "1") (pinfunction "~{SHDN}_1") (pintype "passive"))
      (node (ref "U8") (pin "3") (pinfunction "3_3") (pintype "passive"))
    )
    (net (code "10") (name "Net-(C1-+)") (class "Default")
      (node (ref "C1") (pin "1") (pinfunction "+_1") (pintype "passive"))
      (node (ref "C5") (pin "2") (pinfunction "2_2") (pintype "passive"))
      (node (ref "L2") (pin "P$1") (pinfunction "1_P$1") (pintype "passive"))
      (node (ref "X2") (pin "1") (pinfunction "KL_1") (pintype "passive"))
    )
    (net (code "11") (name "Net-(C2-Pad1)") (class "Default")
      (node (ref "C2") (pin "1") (pinfunction "1_1") (pintype "passive"))
      (node (ref "D1") (pin "A") (pinfunction "A_A") (pintype "passive"))
      (node (ref "R3") (pin "2") (pinfunction "2_2") (pintype "passive"))
    )
    (net (code "12") (name "Net-(C3-Pad1)") (class "Default")
      (node (ref "C3") (pin "1") (pinfunction "1_1") (pintype "passive"))
      (node (ref "D2") (pin "C") (pinfunction "C_C") (pintype "passive"))
      (node (ref "R2") (pin "1") (pinfunction "1_1") (pintype "passive"))
    )
    (net (code "13") (name "Net-(C4-Pad1)") (class "Default")
      (node (ref "C4") (pin "1") (pinfunction "1_1") (pintype "passive"))
      (node (ref "L1") (pin "1") (pinfunction "1_1") (pintype "passive"))
      (node (ref "X1") (pin "1") (pinfunction "1_1") (pintype "passive"))
    )
    (net (code "14") (name "Net-(C6-Pad1)") (class "Default")
      (node (ref "C6") (pin "1") (pinfunction "1_1") (pintype "passive"))
      (node (ref "L1") (pin "2") (pinfunction "2_2") (pintype "passive"))
      (node (ref "L3") (pin "1") (pinfunction "1_1") (pintype "passive"))
    )
    (net (code "15") (name "Net-(C7-Pad2)") (class "Default")
      (node (ref "C7") (pin "2") (pinfunction "2_2") (pintype "passive"))
      (node (ref "R3") (pin "1") (pinfunction "1_1") (pintype "passive"))
      (node (ref "U7") (pin "3") (pinfunction "3_3") (pintype "passive"))
    )
    (net (code "16") (name "Net-(C10-Pad1)") (class "Default")
      (node (ref "C10") (pin "1") (pinfunction "1_1") (pintype "passive"))
      (node (ref "L3") (pin "2") (pinfunction "2_2") (pintype "passive"))
      (node (ref "L4") (pin "1") (pinfunction "1_1") (pintype "passive"))
    )
    (net (code "17") (name "Net-(C11-Pad1)") (class "Default")
      (node (ref "C11") (pin "1") (pinfunction "1_1") (pintype "passive"))
      (node (ref "R10") (pin "1") (pinfunction "1_1") (pintype "passive"))
      (node (ref "R14") (pin "1") (pinfunction "1_1") (pintype "passive"))
    )
    (net (code "18") (name "Net-(C11-Pad2)") (class "Default")
      (node (ref "C11") (pin "2") (pinfunction "2_2") (pintype "passive"))
      (node (ref "D1") (pin "C") (pinfunction "C_C") (pintype "passive"))
      (node (ref "R4") (pin "1") (pinfunction "1_1") (pintype "passive"))
    )
    (net (code "19") (name "Net-(C14-Pad1)") (class "Default")
      (node (ref "C14") (pin "1") (pinfunction "1_1") (pintype "passive"))
      (node (ref "L4") (pin "2") (pinfunction "2_2") (pintype "passive"))
      (node (ref "R7") (pin "2") (pinfunction "2_2") (pintype "passive"))
    )
    (net (code "20") (name "Net-(C21-Pad2)") (class "Default")
      (node (ref "C21") (pin "2") (pinfunction "2_2") (pintype "passive"))
      (node (ref "R13") (pin "1") (pinfunction "1_1") (pintype "passive"))
    )
    (net (code "21") (name "Net-(C22-+)") (class "Default")
      (node (ref "C22") (pin "1") (pinfunction "+_1") (pintype "passive"))
      (node (ref "C27") (pin "2") (pinfunction "2_2") (pintype "passive"))
      (node (ref "L6") (pin "-") (pinfunction "2_-") (pintype "passive"))
      (node (ref "L8") (pin "+") (pinfunction "1_+") (pintype "passive"))
      (node (ref "R15") (pin "2") (pinfunction "2_2") (pintype "passive"))
    )
    (net (code "22") (name "Net-(C24-Pad2)") (class "Default")
      (node (ref "C24") (pin "2") (pinfunction "2_2") (pintype "passive"))
      (node (ref "JP3") (pin "1") (pinfunction "1_1") (pintype "passive"))
      (node (ref "R11") (pin "1") (pinfunction "1_1") (pintype "passive"))
      (node (ref "R12") (pin "2") (pinfunction "2_2") (pintype "passive"))
    )
    (net (code "23") (name "Net-(C30-Pad1)") (class "Default")
      (node (ref "C30") (pin "1") (pinfunction "1_1") (pintype "passive"))
      (node (ref "L15") (pin "2") (pinfunction "2_2") (pintype "passive"))
    )
    (net (code "24") (name "Net-(C30-Pad2)") (class "Default")
      (node (ref "C30") (pin "2") (pinfunction "2_2") (pintype "passive"))
      (node (ref "C31") (pin "1") (pinfunction "1_1") (pintype "passive"))
      (node (ref "L11") (pin "2") (pinfunction "2_2") (pintype "passive"))
      (node (ref "R21") (pin "2") (pinfunction "2_2") (pintype "passive"))
    )
    (net (code "25") (name "Net-(C40-Pad2)") (class "Default")
      (node (ref "C40") (pin "2") (pinfunction "2_2") (pintype "passive"))
      (node (ref "X4") (pin "1") (pinfunction "1_1") (pintype "passive"))
    )
    (net (code "26") (name "Net-(C41-Pad1)") (class "Default")
      (node (ref "C41") (pin "1") (pinfunction "1_1") (pintype "passive"))
      (node (ref "D6") (pin "C") (pinfunction "C_C") (pintype "passive"))
      (node (ref "JP5") (pin "1") (pinfunction "1_1") (pintype "passive"))
      (node (ref "R24") (pin "2") (pinfunction "2_2") (pintype "passive"))
    )
    (net (code "27") (name "Net-(C45-Pad1)") (class "Default")
      (node (ref "C45") (pin "1") (pinfunction "1_1") (pintype "passive"))
      (node (ref "D8") (pin "C") (pinfunction "C_C") (pintype "passive"))
      (node (ref "JP7") (pin "1") (pinfunction "1_1") (pintype "passive"))
      (node (ref "R1") (pin "1") (pinfunction "1_1") (pintype "passive"))
    )
    (net (code "28") (name "Net-(D3-C)") (class "Default")
      (node (ref "D3") (pin "1") (pinfunction "C_1") (pintype "passive"))
      (node (ref "L6") (pin "+") (pinfunction "1_+") (pintype "passive"))
      (node (ref "U6") (pin "2") (pinfunction "OUT_2") (pintype "output"))
    )
    (net (code "29") (name "Net-(D4-C)") (class "Default")
      (node (ref "D4") (pin "1") (pinfunction "C_1") (pintype "passive"))
      (node (ref "TP1") (pin "TP") (pinfunction "PP_TP") (pintype "input"))
      (node (ref "X3") (pin "1") (pinfunction "KL_1") (pintype "passive"))
    )
    (net (code "30") (name "Net-(D5-A)") (class "Default")
      (node (ref "C37") (pin "1") (pinfunction "1_1") (pintype "passive"))
      (node (ref "D5") (pin "2") (pinfunction "A_2") (pintype "passive"))
      (node (ref "L14") (pin "P$1") (pinfunction "1_P$1") (pintype "passive"))
    )
    (net (code "31") (name "Net-(D5-C)") (class "Default")
      (node (ref "C40") (pin "1") (pinfunction "1_1") (pintype "passive"))
      (node (ref "C42") (pin "1") (pinfunction "1_1") (pintype "passive"))
      (node (ref "D5") (pin "1") (pinfunction "C_1") (pintype "passive"))
      (node (ref "L13") (pin "1") (pinfunction "1_1") (pintype "passive"))
    )
    (net (code "32") (name "Net-(D6-PadA)") (class "Default")
      (node (ref "D6") (pin "A") (pinfunction "A_A") (pintype "passive"))
      (node (ref "R36") (pin "2") (pinfunction "2_2") (pintype "passive"))
      (node (ref "R38") (pin "2") (pinfunction "2_2") (pintype "passive"))
    )
    (net (code "33") (name "Net-(D7-A)") (class "Default")
      (node (ref "C43") (pin "1") (pinfunction "1_1") (pintype "passive"))
      (node (ref "C49") (pin "2") (pinfunction "2_2") (pintype "passive"))
      (node (ref "D7") (pin "2") (pinfunction "A_2") (pintype "passive"))
      (node (ref "L13") (pin "2") (pinfunction "2_2") (pintype "passive"))
    )
    (net (code "34") (name "Net-(D8-PadA)") (class "Default")
      (node (ref "D8") (pin "A") (pinfunction "A_A") (pintype "passive"))
      (node (ref "R28") (pin "2") (pinfunction "2_2") (pintype "passive"))
      (node (ref "R29") (pin "2") (pinfunction "2_2") (pintype "passive"))
    )
    (net (code "35") (name "Net-(JP1-Pad1)") (class "Default")
      (node (ref "JP1") (pin "1") (pinfunction "1_1") (pintype "passive"))
      (node (ref "R23") (pin "1") (pinfunction "1_1") (pintype "passive"))
      (node (ref "U7") (pin "1") (pinfunction "1_1") (pintype "passive"))
    )
    (net (code "36") (name "Net-(JP2-Pad1)") (class "Default")
      (node (ref "JP2") (pin "1") (pinfunction "1_1") (pintype "passive"))
      (node (ref "R31") (pin "1") (pinfunction "1_1") (pintype "passive"))
      (node (ref "U8") (pin "1") (pinfunction "1_1") (pintype "passive"))
    )
    (net (code "37") (name "Net-(JP8-Pad1)") (class "Default")
      (node (ref "JP8") (pin "1") (pinfunction "1_1") (pintype "passive"))
      (node (ref "R27") (pin "1") (pinfunction "1_1") (pintype "passive"))
      (node (ref "R35") (pin "2") (pinfunction "2_2") (pintype "passive"))
    )
    (net (code "38") (name "Net-(L7-Pad1)") (class "Default")
      (node (ref "L7") (pin "1") (pinfunction "1_1") (pintype "passive"))
      (node (ref "R13") (pin "2") (pinfunction "2_2") (pintype "passive"))
    )
    (net (code "39") (name "Net-(L10-1)") (class "Default")
      (node (ref "C32") (pin "1") (pinfunction "1_1") (pintype "passive"))
      (node (ref "L10") (pin "P$1") (pinfunction "1_P$1") (pintype "passive"))
      (node (ref "R20") (pin "1") (pinfunction "1_1") (pintype "passive"))
    )
    (net (code "40") (name "Net-(L10-2)") (class "Default")
      (node (ref "C35") (pin "1") (pinfunction "1_1") (pintype "passive"))
      (node (ref "L10") (pin "P$2") (pinfunction "2_P$2") (pintype "passive"))
      (node (ref "L12") (pin "P$1") (pinfunction "1_P$1") (pintype "passive"))
    )
    (net (code "41") (name "Net-(L14-2)") (class "Default")
      (node (ref "C39") (pin "2") (pinfunction "2_2") (pintype "passive"))
      (node (ref "L14") (pin "P$2") (pinfunction "2_P$2") (pintype "passive"))
      (node (ref "U9") (pin "3") (pinfunction "3_3") (pintype "passive"))
    )
    (net (code "42") (name "Net-(R20-Pad2)") (class "Default")
      (node (ref "R20") (pin "2") (pinfunction "2_2") (pintype "passive"))
      (node (ref "U2") (pin "OUT") (pinfunction "OUT_OUT") (pintype "output"))
    )
    (net (code "43") (name "Net-(R33-Pad1)") (class "Default")
      (node (ref "R33") (pin "1") (pinfunction "1_1") (pintype "passive"))
      (node (ref "R39") (pin "1") (pinfunction "1_1") (pintype "passive"))
      (node (ref "T2") (pin "C") (pinfunction "C_C") (pintype "passive"))
    )
    (net (code "44") (name "Net-(R34-Pad1)") (class "Default")
      (node (ref "R34") (pin "1") (pinfunction "1_1") (pintype "passive"))
      (node (ref "T2") (pin "B") (pinfunction "B_B") (pintype "passive"))
    )
    (net (code "45") (name "Net-(R34-Pad2)") (class "Default")
      (node (ref "R34") (pin "2") (pinfunction "2_2") (pintype "passive"))
      (node (ref "R37") (pin "2") (pinfunction "2_2") (pintype "passive"))
      (node (ref "T1") (pin "C") (pinfunction "C_C") (pintype "passive"))
    )
    (net (code "46") (name "Net-(R35-Pad1)") (class "Default")
      (node (ref "R35") (pin "1") (pinfunction "1_1") (pintype "passive"))
      (node (ref "T1") (pin "B") (pinfunction "B_B") (pintype "passive"))
    )
    (net (code "47") (name "Net-(TP2-PP)") (class "Default")
      (node (ref "C28") (pin "1") (pinfunction "1_1") (pintype "passive"))
      (node (ref "C59") (pin "1") (pinfunction "1_1") (pintype "passive"))
      (node (ref "L15") (pin "1") (pinfunction "1_1") (pintype "passive"))
      (node (ref "L9") (pin "2") (pinfunction "2_2") (pintype "passive"))
      (node (ref "TP2") (pin "TP") (pinfunction "PP_TP") (pintype "input"))
    )
    (net (code "48") (name "Net-(TP3-PP)") (class "Default")
      (node (ref "C23") (pin "2") (pinfunction "2_2") (pintype "passive"))
      (node (ref "L7") (pin "2") (pinfunction "2_2") (pintype "passive"))
      (node (ref "TP3") (pin "TP") (pinfunction "PP_TP") (pintype "input"))
      (node (ref "U1") (pin "1") (pinfunction "IN_1") (pintype "input"))
    )
    (net (code "49") (name "Net-(U1-OUT)") (class "Default")
      (node (ref "C16") (pin "1") (pinfunction "1_1") (pintype "passive"))
      (node (ref "L5") (pin "RF-DC") (pinfunction "RF-DC_RF-DC") (pintype "passive"))
      (node (ref "U1") (pin "3") (pinfunction "OUT_3") (pintype "output"))
    )
    (net (code "50") (name "Net-(U3-DQ)") (class "Default")
      (node (ref "JP4") (pin "1") (pinfunction "1_1") (pintype "passive"))
      (node (ref "R22") (pin "1") (pinfunction "1_1") (pintype "passive"))
      (node (ref "U3") (pin "2") (pinfunction "DQ_2") (pintype "output"))
    )
    (net (code "51") (name "Net-(U4-ADJ)") (class "Default")
      (node (ref "R25") (pin "2") (pinfunction "2_2") (pintype "passive"))
      (node (ref "R26") (pin "1") (pinfunction "1_1") (pintype "passive"))
      (node (ref "U4") (pin "5") (pinfunction "ADJ_5") (pintype "passive"))
    )
    (net (code "52") (name "Net-(U5-SCL)") (class "Default")
      (node (ref "JP6") (pin "1") (pinfunction "1_1") (pintype "passive"))
      (node (ref "R32") (pin "2") (pinfunction "2_2") (pintype "passive"))
      (node (ref "U5") (pin "2") (pinfunction "SCL_2") (pintype "input"))
    )
    (net (code "53") (name "Net-(U5-SDA)") (class "Default")
      (node (ref "JP6") (pin "2") (pinfunction "2_2") (pintype "passive"))
      (node (ref "R30") (pin "2") (pinfunction "2_2") (pintype "passive"))
      (node (ref "U5") (pin "3") (pinfunction "SDA_3") (pintype "bidirectional"))
    )
    (net (code "54") (name "Net-(U6-FB)") (class "Default")
      (node (ref "C27") (pin "1") (pinfunction "1_1") (pintype "passive"))
      (node (ref "R15") (pin "1") (pinfunction "1_1") (pintype "passive"))
      (node (ref "R16") (pin "2") (pinfunction "2_2") (pintype "passive"))
      (node (ref "U6") (pin "4") (pinfunction "FB_4") (pintype "input"))
    )
    (net (code "55") (name "Net-(U10-RF1)") (class "Default")
      (node (ref "R10") (pin "2") (pinfunction "2_2") (pintype "passive"))
      (node (ref "R9") (pin "1") (pinfunction "1_1") (pintype "passive"))
      (node (ref "U10") (pin "3") (pinfunction "RF1_3") (pintype "bidirectional"))
    )
    (net (code "56") (name "Net-(U10-RF2)") (class "Default")
      (node (ref "C51") (pin "2") (pinfunction "2_2") (pintype "passive"))
      (node (ref "U10") (pin "10") (pinfunction "RF2_10") (pintype "bidirectional"))
    )
    (net (code "57") (name "Net-(U10-RTN_1)") (class "Default")
      (node (ref "C52") (pin "1") (pinfunction "1_1") (pintype "passive"))
      (node (ref "U10") (pin "5") (pinfunction "RTN_1_5") (pintype "bidirectional"))
    )
    (net (code "58") (name "Net-(U10-RTN_2)") (class "Default")
      (node (ref "C53") (pin "1") (pinfunction "1_1") (pintype "passive"))
      (node (ref "U10") (pin "6") (pinfunction "RTN_2_6") (pintype "bidirectional"))
    )
    (net (code "59") (name "Net-(U10-RTN_3)") (class "Default")
      (node (ref "C54") (pin "1") (pinfunction "1_1") (pintype "passive"))
      (node (ref "U10") (pin "8") (pinfunction "RTN_3_8") (pintype "bidirectional"))
    )
    (net (code "60") (name "Net-(U10-VCTRL)") (class "Default")
      (node (ref "C56") (pin "1") (pinfunction "1_1") (pintype "passive"))
      (node (ref "R8") (pin "1") (pinfunction "1_1") (pintype "passive"))
      (node (ref "U10") (pin "14") (pinfunction "VCTRL_14") (pintype "bidirectional"))
    )
    (net (code "61") (name "Net-(U10-VDD)") (class "Default")
      (node (ref "C55") (pin "1") (pinfunction "1_1") (pintype "passive"))
      (node (ref "R6") (pin "2") (pinfunction "2_2") (pintype "passive"))
      (node (ref "U10") (pin "15") (pinfunction "VDD_15") (pintype "bidirectional"))
    )
    (net (code "62") (name "Net-(U11-RF1)") (class "Default")
      (node (ref "C23") (pin "1") (pinfunction "1_1") (pintype "passive"))
      (node (ref "U11") (pin "3") (pinfunction "RF1_3") (pintype "bidirectional"))
    )
    (net (code "63") (name "Net-(U11-RF2)") (class "Default")
      (node (ref "C59") (pin "2") (pinfunction "2_2") (pintype "passive"))
      (node (ref "U11") (pin "10") (pinfunction "RF2_10") (pintype "bidirectional"))
    )
    (net (code "64") (name "Net-(U11-RTN_1)") (class "Default")
      (node (ref "C60") (pin "1") (pinfunction "1_1") (pintype "passive"))
      (node (ref "U11") (pin "5") (pinfunction "RTN_1_5") (pintype "bidirectional"))
    )
    (net (code "65") (name "Net-(U11-RTN_2)") (class "Default")
      (node (ref "C61") (pin "1") (pinfunction "1_1") (pintype "passive"))
      (node (ref "U11") (pin "6") (pinfunction "RTN_2_6") (pintype "bidirectional"))
    )
    (net (code "66") (name "Net-(U11-RTN_3)") (class "Default")
      (node (ref "C62") (pin "1") (pinfunction "1_1") (pintype "passive"))
      (node (ref "U11") (pin "8") (pinfunction "RTN_3_8") (pintype "bidirectional"))
    )
    (net (code "67") (name "Net-(U11-VCTRL)") (class "Default")
      (node (ref "C64") (pin "1") (pinfunction "1_1") (pintype "passive"))
      (node (ref "R18") (pin "1") (pinfunction "1_1") (pintype "passive"))
      (node (ref "U11") (pin "14") (pinfunction "VCTRL_14") (pintype "bidirectional"))
    )
    (net (code "68") (name "Net-(U11-VDD)") (class "Default")
      (node (ref "C63") (pin "1") (pinfunction "1_1") (pintype "passive"))
      (node (ref "R17") (pin "2") (pinfunction "2_2") (pintype "passive"))
      (node (ref "U11") (pin "15") (pinfunction "VDD_15") (pintype "bidirectional"))
    )
    (net (code "69") (name "PA-IN") (class "Default")
      (node (ref "C51") (pin "1") (pinfunction "1_1") (pintype "passive"))
      (node (ref "U2") (pin "IN") (pinfunction "IN_IN") (pintype "input"))
    )
    (net (code "70") (name "RX-IN") (class "Default")
      (node (ref "C49") (pin "1") (pinfunction "1_1") (pintype "passive"))
      (node (ref "R19") (pin "1") (pinfunction "1_1") (pintype "passive"))
      (node (ref "R21") (pin "1") (pinfunction "1_1") (pintype "passive"))
    )
    (net (code "71") (name "RX-INAF") (class "Default")
      (node (ref "C16") (pin "2") (pinfunction "2_2") (pintype "passive"))
      (node (ref "D2") (pin "A") (pinfunction "A_A") (pintype "passive"))
      (node (ref "R19") (pin "2") (pinfunction "2_2") (pintype "passive"))
      (node (ref "R5") (pin "2") (pinfunction "2_2") (pintype "passive"))
      (node (ref "TP4") (pin "TP") (pinfunction "PP_TP") (pintype "input"))
    )
    (net (code "72") (name "TX-IN{slash}RX-OUT") (class "Default")
      (node (ref "C2") (pin "2") (pinfunction "2_2") (pintype "passive"))
      (node (ref "C3") (pin "2") (pinfunction "2_2") (pintype "passive"))
      (node (ref "R7") (pin "1") (pinfunction "1_1") (pintype "passive"))
      (node (ref "TP5") (pin "TP") (pinfunction "PP_TP") (pintype "input"))
    )
    (net (code "73") (name "TX-OUT") (class "Default")
      (node (ref "C36") (pin "1") (pinfunction "1_1") (pintype "passive"))
      (node (ref "C37") (pin "2") (pinfunction "2_2") (pintype "passive"))
      (node (ref "L12") (pin "P$2") (pinfunction "2_P$2") (pintype "passive"))
    )
    (net (code "74") (name "VBIAS") (class "Default")
      (node (ref "R33") (pin "2") (pinfunction "2_2") (pintype "passive"))
      (node (ref "R39") (pin "2") (pinfunction "2_2") (pintype "passive"))
      (node (ref "U9") (pin "1") (pinfunction "1_1") (pintype "passive"))
    )
    (net (code "75") (name "VGG") (class "Default")
      (node (ref "C19") (pin "2") (pinfunction "2_2") (pintype "passive"))
      (node (ref "C20") (pin "+") (pinfunction "+_+") (pintype "passive"))
      (node (ref "U2") (pin "VGG") (pinfunction "VGG_VGG") (pintype "power_in"))
      (node (ref "U5") (pin "9") (pinfunction "VOUTD_9") (pintype "output"))
    )
    (net (code "76") (name "VOUTA") (class "Default")
      (node (ref "C46") (pin "1") (pinfunction "1_1") (pintype "passive"))
      (node (ref "R18") (pin "2") (pinfunction "2_2") (pintype "passive"))
      (node (ref "U5") (pin "6") (pinfunction "VOUTA_6") (pintype "output"))
    )
    (net (code "77") (name "VOUTB") (class "Default")
      (node (ref "C58") (pin "1") (pinfunction "1_1") (pintype "passive"))
      (node (ref "R8") (pin "2") (pinfunction "2_2") (pintype "passive"))
      (node (ref "U5") (pin "7") (pinfunction "VOUTB_7") (pintype "output"))
    )
    (net (code "78") (name "VOUTC") (class "Default")
      (node (ref "U5") (pin "8") (pinfunction "VOUTC_8") (pintype "output"))
    )
    (net (code "79") (name "unconnected-(L5-PadNC1)") (class "Default")
      (node (ref "L5") (pin "NC1") (pinfunction "NC1_NC1") (pintype "no_connect"))
    )
    (net (code "80") (name "unconnected-(L5-PadNC2)") (class "Default")
      (node (ref "L5") (pin "NC2") (pinfunction "NC2_NC2") (pintype "no_connect"))
    )
    (net (code "81") (name "unconnected-(U5-RDY{slash}~{BSY}-Pad5)") (class "Default")
      (node (ref "U5") (pin "5") (pinfunction "RDY/~{BSY}_5") (pintype "output"))
    )
  )
)
